# ButtonLed8.net
KiCad netlist of a schematic drawn in EAGLE
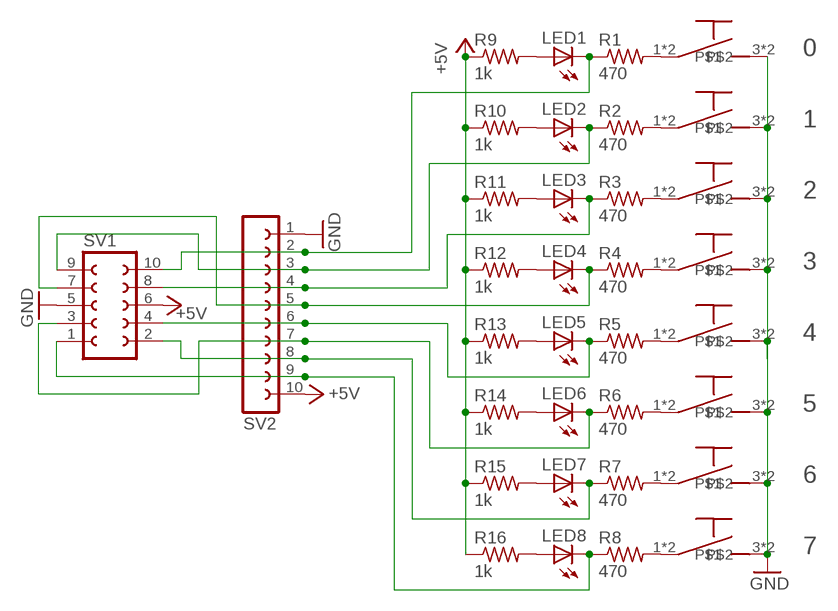
[diagram p0: schematic, sheet 1]

(export (version "E")
  (design (tool "Eeschema 10.0.6"))
  (components
    (comp (ref "LED1")
      (value "LED3MM")
      (footprint "eagle-import:LED3MM")
      (libsource (lib "eagle-import") (part "LED3MM"))
    )
    (comp (ref "LED2")
      (value "LED3MM")
      (footprint "eagle-import:LED3MM")
      (libsource (lib "eagle-import") (part "LED3MM"))
    )
    (comp (ref "LED3")
      (value "LED3MM")
      (footprint "eagle-import:LED3MM")
      (libsource (lib "eagle-import") (part "LED3MM"))
    )
    (comp (ref "LED4")
      (value "LED3MM")
      (footprint "eagle-import:LED3MM")
      (libsource (lib "eagle-import") (part "LED3MM"))
    )
    (comp (ref "LED5")
      (value "LED3MM")
      (footprint "eagle-import:LED3MM")
      (libsource (lib "eagle-import") (part "LED3MM"))
    )
    (comp (ref "LED6")
      (value "LED3MM")
      (footprint "eagle-import:LED3MM")
      (libsource (lib "eagle-import") (part "LED3MM"))
    )
    (comp (ref "LED7")
      (value "LED3MM")
      (footprint "eagle-import:LED3MM")
      (libsource (lib "eagle-import") (part "LED3MM"))
    )
    (comp (ref "LED8")
      (value "LED3MM")
      (footprint "eagle-import:LED3MM")
      (libsource (lib "eagle-import") (part "LED3MM"))
    )
    (comp (ref "R1")
      (value "470")
      (footprint "eagle-import:0204_7")
      (libsource (lib "eagle-import") (part "R-US_0204/7"))
    )
    (comp (ref "R2")
      (value "470")
      (footprint "eagle-import:0204_7")
      (libsource (lib "eagle-import") (part "R-US_0204/7"))
    )
    (comp (ref "R3")
      (value "470")
      (footprint "eagle-import:0204_7")
      (libsource (lib "eagle-import") (part "R-US_0204/7"))
    )
    (comp (ref "R4")
      (value "470")
      (footprint "eagle-import:0204_7")
      (libsource (lib "eagle-import") (part "R-US_0204/7"))
    )
    (comp (ref "R5")
      (value "470")
      (footprint "eagle-import:0204_7")
      (libsource (lib "eagle-import") (part "R-US_0204/7"))
    )
    (comp (ref "R6")
      (value "470")
      (footprint "eagle-import:0204_7")
      (libsource (lib "eagle-import") (part "R-US_0204/7"))
    )
    (comp (ref "R7")
      (value "470")
      (footprint "eagle-import:0204_7")
      (libsource (lib "eagle-import") (part "R-US_0204/7"))
    )
    (comp (ref "R8")
      (value "470")
      (footprint "eagle-import:0204_7")
      (libsource (lib "eagle-import") (part "R-US_0204/7"))
    )
    (comp (ref "R9")
      (value "1k")
      (footprint "eagle-import:0204_7")
      (libsource (lib "eagle-import") (part "R-US_0204/7"))
    )
    (comp (ref "R10")
      (value "1k")
      (footprint "eagle-import:0204_7")
      (libsource (lib "eagle-import") (part "R-US_0204/7"))
    )
    (comp (ref "R11")
      (value "1k")
      (footprint "eagle-import:0204_7")
      (libsource (lib "eagle-import") (part "R-US_0204/7"))
    )
    (comp (ref "R12")
      (value "1k")
      (footprint "eagle-import:0204_7")
      (libsource (lib "eagle-import") (part "R-US_0204/7"))
    )
    (comp (ref "R13")
      (value "1k")
      (footprint "eagle-import:0204_7")
      (libsource (lib "eagle-import") (part "R-US_0204/7"))
    )
    (comp (ref "R14")
      (value "1k")
      (footprint "eagle-import:0204_7")
      (libsource (lib "eagle-import") (part "R-US_0204/7"))
    )
    (comp (ref "R15")
      (value "1k")
      (footprint "eagle-import:0204_7")
      (libsource (lib "eagle-import") (part "R-US_0204/7"))
    )
    (comp (ref "R16")
      (value "1k")
      (footprint "eagle-import:0204_7")
      (libsource (lib "eagle-import") (part "R-US_0204/7"))
    )
    (comp (ref "SV1")
      (value "FE05-2")
      (footprint "eagle-import:FE05-2")
      (fields (field (name "OC_FARNELL") "unknown") (field (name "OC_NEWARK") "unknown"))
      (libsource (lib "eagle-import") (part "FE05-2"))
    )
    (comp (ref "SV2")
      (value "FE10-1")
      (footprint "eagle-import:FE10")
      (fields (field (name "OC_FARNELL") "unknown") (field (name "OC_NEWARK") "unknown"))
      (libsource (lib "eagle-import") (part "FE10-1"))
    )
    (comp (ref "U$1")
      (value "BUTTON")
      (footprint "eagle-import:SPARKFUN_TACTILE-PTH")
      (libsource (lib "eagle-import") (part "BUTTON"))
    )
    (comp (ref "U$2")
      (value "BUTTON")
      (footprint "eagle-import:SPARKFUN_TACTILE-PTH")
      (libsource (lib "eagle-import") (part "BUTTON"))
    )
    (comp (ref "U$3")
      (value "BUTTON")
      (footprint "eagle-import:SPARKFUN_TACTILE-PTH")
      (libsource (lib "eagle-import") (part "BUTTON"))
    )
    (comp (ref "U$4")
      (value "BUTTON")
      (footprint "eagle-import:SPARKFUN_TACTILE-PTH")
      (libsource (lib "eagle-import") (part "BUTTON"))
    )
    (comp (ref "U$5")
      (value "BUTTON")
      (footprint "eagle-import:SPARKFUN_TACTILE-PTH")
      (libsource (lib "eagle-import") (part "BUTTON"))
    )
    (comp (ref "U$6")
      (value "BUTTON")
      (footprint "eagle-import:SPARKFUN_TACTILE-PTH")
      (libsource (lib "eagle-import") (part "BUTTON"))
    )
    (comp (ref "U$7")
      (value "BUTTON")
      (footprint "eagle-import:SPARKFUN_TACTILE-PTH")
      (libsource (lib "eagle-import") (part "BUTTON"))
    )
    (comp (ref "U$8")
      (value "BUTTON")
      (footprint "eagle-import:SPARKFUN_TACTILE-PTH")
      (libsource (lib "eagle-import") (part "BUTTON"))
    )
  )
  (nets
    (net (code "1") (name "+5V") (class "Default")
      (node (ref "R10") (pin "1") (pinfunction "1_1") (pintype "passive"))
      (node (ref "R11") (pin "1") (pinfunction "1_1") (pintype "passive"))
      (node (ref "R12") (pin "1") (pinfunction "1_1") (pintype "passive"))
      (node (ref "R13") (pin "1") (pinfunction "1_1") (pintype "passive"))
      (node (ref "R14") (pin "1") (pinfunction "1_1") (pintype "passive"))
      (node (ref "R15") (pin "1") (pinfunction "1_1") (pintype "passive"))
      (node (ref "R16") (pin "1") (pinfunction "1_1") (pintype "passive"))
      (node (ref "R9") (pin "1") (pinfunction "1_1") (pintype "passive"))
      (node (ref "SV1") (pin "6") (pinfunction "6_6") (pintype "passive"))
      (node (ref "SV2") (pin "10") (pinfunction "10_10") (pintype "passive"))
    )
    (net (code "2") (name "GND") (class "Default")
      (node (ref "SV1") (pin "5") (pinfunction "5_5") (pintype "passive"))
      (node (ref "SV2") (pin "1") (pinfunction "1_1") (pintype "passive"))
      (node (ref "U$1") (pin "3") (pinfunction "P$2_3") (pintype "bidirectional"))
      (node (ref "U$1") (pin "4") (pinfunction "P$2_4") (pintype "bidirectional"))
      (node (ref "U$2") (pin "3") (pinfunction "P$2_3") (pintype "bidirectional"))
      (node (ref "U$2") (pin "4") (pinfunction "P$2_4") (pintype "bidirectional"))
      (node (ref "U$3") (pin "3") (pinfunction "P$2_3") (pintype "bidirectional"))
      (node (ref "U$3") (pin "4") (pinfunction "P$2_4") (pintype "bidirectional"))
      (node (ref "U$4") (pin "3") (pinfunction "P$2_3") (pintype "bidirectional"))
      (node (ref "U$4") (pin "4") (pinfunction "P$2_4") (pintype "bidirectional"))
      (node (ref "U$5") (pin "3") (pinfunction "P$2_3") (pintype "bidirectional"))
      (node (ref "U$5") (pin "4") (pinfunction "P$2_4") (pintype "bidirectional"))
      (node (ref "U$6") (pin "3") (pinfunction "P$2_3") (pintype "bidirectional"))
      (node (ref "U$6") (pin "4") (pinfunction "P$2_4") (pintype "bidirectional"))
      (node (ref "U$7") (pin "3") (pinfunction "P$2_3") (pintype "bidirectional"))
      (node (ref "U$7") (pin "4") (pinfunction "P$2_4") (pintype "bidirectional"))
      (node (ref "U$8") (pin "3") (pinfunction "P$2_3") (pintype "bidirectional"))
      (node (ref "U$8") (pin "4") (pinfunction "P$2_4") (pintype "bidirectional"))
    )
    (net (code "3") (name "Net-(LED1-C)") (class "Default")
      (node (ref "LED1") (pin "K") (pinfunction "C_K") (pintype "passive"))
      (node (ref "R1") (pin "1") (pinfunction "1_1") (pintype "passive"))
      (node (ref "SV1") (pin "10") (pinfunction "10_10") (pintype "passive"))
      (node (ref "SV2") (pin "2") (pinfunction "2_2") (pintype "passive"))
    )
    (net (code "4") (name "Net-(LED1-PadA)") (class "Default")
      (node (ref "LED1") (pin "A") (pinfunction "A_A") (pintype "passive"))
      (node (ref "R9") (pin "2") (pinfunction "2_2") (pintype "passive"))
    )
    (net (code "5") (name "Net-(LED2-C)") (class "Default")
      (node (ref "LED2") (pin "K") (pinfunction "C_K") (pintype "passive"))
      (node (ref "R2") (pin "1") (pinfunction "1_1") (pintype "passive"))
      (node (ref "SV1") (pin "9") (pinfunction "9_9") (pintype "passive"))
      (node (ref "SV2") (pin "3") (pinfunction "3_3") (pintype "passive"))
    )
    (net (code "6") (name "Net-(LED2-PadA)") (class "Default")
      (node (ref "LED2") (pin "A") (pinfunction "A_A") (pintype "passive"))
      (node (ref "R10") (pin "2") (pinfunction "2_2") (pintype "passive"))
    )
    (net (code "7") (name "Net-(LED3-C)") (class "Default")
      (node (ref "LED3") (pin "K") (pinfunction "C_K") (pintype "passive"))
      (node (ref "R3") (pin "1") (pinfunction "1_1") (pintype "passive"))
      (node (ref "SV1") (pin "8") (pinfunction "8_8") (pintype "passive"))
      (node (ref "SV2") (pin "4") (pinfunction "4_4") (pintype "passive"))
    )
    (net (code "8") (name "Net-(LED3-PadA)") (class "Default")
      (node (ref "LED3") (pin "A") (pinfunction "A_A") (pintype "passive"))
      (node (ref "R11") (pin "2") (pinfunction "2_2") (pintype "passive"))
    )
    (net (code "9") (name "Net-(LED4-C)") (class "Default")
      (node (ref "LED4") (pin "K") (pinfunction "C_K") (pintype "passive"))
      (node (ref "R4") (pin "1") (pinfunction "1_1") (pintype "passive"))
      (node (ref "SV1") (pin "7") (pinfunction "7_7") (pintype "passive"))
      (node (ref "SV2") (pin "5") (pinfunction "5_5") (pintype "passive"))
    )
    (net (code "10") (name "Net-(LED4-PadA)") (class "Default")
      (node (ref "LED4") (pin "A") (pinfunction "A_A") (pintype "passive"))
      (node (ref "R12") (pin "2") (pinfunction "2_2") (pintype "passive"))
    )
    (net (code "11") (name "Net-(LED5-C)") (class "Default")
      (node (ref "LED5") (pin "K") (pinfunction "C_K") (pintype "passive"))
      (node (ref "R5") (pin "1") (pinfunction "1_1") (pintype "passive"))
      (node (ref "SV1") (pin "4") (pinfunction "4_4") (pintype "passive"))
      (node (ref "SV2") (pin "6") (pinfunction "6_6") (pintype "passive"))
    )
    (net (code "12") (name "Net-(LED5-PadA)") (class "Default")
      (node (ref "LED5") (pin "A") (pinfunction "A_A") (pintype "passive"))
      (node (ref "R13") (pin "2") (pinfunction "2_2") (pintype "passive"))
    )
    (net (code "13") (name "Net-(LED6-C)") (class "Default")
      (node (ref "LED6") (pin "K") (pinfunction "C_K") (pintype "passive"))
      (node (ref "R6") (pin "1") (pinfunction "1_1") (pintype "passive"))
      (node (ref "SV1") (pin "3") (pinfunction "3_3") (pintype "passive"))
      (node (ref "SV2") (pin "7") (pinfunction "7_7") (pintype "passive"))
    )
    (net (code "14") (name "Net-(LED6-PadA)") (class "Default")
      (node (ref "LED6") (pin "A") (pinfunction "A_A") (pintype "passive"))
      (node (ref "R14") (pin "2") (pinfunction "2_2") (pintype "passive"))
    )
    (net (code "15") (name "Net-(LED7-C)") (class "Default")
      (node (ref "LED7") (pin "K") (pinfunction "C_K") (pintype "passive"))
      (node (ref "R7") (pin "1") (pinfunction "1_1") (pintype "passive"))
      (node (ref "SV1") (pin "2") (pinfunction "2_2") (pintype "passive"))
      (node (ref "SV2") (pin "8") (pinfunction "8_8") (pintype "passive"))
    )
    (net (code "16") (name "Net-(LED7-PadA)") (class "Default")
      (node (ref "LED7") (pin "A") (pinfunction "A_A") (pintype "passive"))
      (node (ref "R15") (pin "2") (pinfunction "2_2") (pintype "passive"))
    )
    (net (code "17") (name "Net-(LED8-C)") (class "Default")
      (node (ref "LED8") (pin "K") (pinfunction "C_K") (pintype "passive"))
      (node (ref "R8") (pin "1") (pinfunction "1_1") (pintype "passive"))
      (node (ref "SV1") (pin "1") (pinfunction "1_1") (pintype "passive"))
      (node (ref "SV2") (pin "9") (pinfunction "9_9") (pintype "passive"))
    )
    (net (code "18") (name "Net-(LED8-PadA)") (class "Default")
      (node (ref "LED8") (pin "A") (pinfunction "A_A") (pintype "passive"))
      (node (ref "R16") (pin "2") (pinfunction "2_2") (pintype "passive"))
    )
    (net (code "19") (name "Net-(R1-Pad2)") (class "Default")
      (node (ref "R1") (pin "2") (pinfunction "2_2") (pintype "passive"))
      (node (ref "U$1") (pin "1") (pinfunction "P$1_1") (pintype "bidirectional"))
      (node (ref "U$1") (pin "2") (pinfunction "P$1_2") (pintype "bidirectional"))
    )
    (net (code "20") (name "Net-(R2-Pad2)") (class "Default")
      (node (ref "R2") (pin "2") (pinfunction "2_2") (pintype "passive"))
      (node (ref "U$2") (pin "1") (pinfunction "P$1_1") (pintype "bidirectional"))
      (node (ref "U$2") (pin "2") (pinfunction "P$1_2") (pintype "bidirectional"))
    )
    (net (code "21") (name "Net-(R3-Pad2)") (class "Default")
      (node (ref "R3") (pin "2") (pinfunction "2_2") (pintype "passive"))
      (node (ref "U$3") (pin "1") (pinfunction "P$1_1") (pintype "bidirectional"))
      (node (ref "U$3") (pin "2") (pinfunction "P$1_2") (pintype "bidirectional"))
    )
    (net (code "22") (name "Net-(R4-Pad2)") (class "Default")
      (node (ref "R4") (pin "2") (pinfunction "2_2") (pintype "passive"))
      (node (ref "U$4") (pin "1") (pinfunction "P$1_1") (pintype "bidirectional"))
      (node (ref "U$4") (pin "2") (pinfunction "P$1_2") (pintype "bidirectional"))
    )
    (net (code "23") (name "Net-(R5-Pad2)") (class "Default")
      (node (ref "R5") (pin "2") (pinfunction "2_2") (pintype "passive"))
      (node (ref "U$5") (pin "1") (pinfunction "P$1_1") (pintype "bidirectional"))
      (node (ref "U$5") (pin "2") (pinfunction "P$1_2") (pintype "bidirectional"))
    )
    (net (code "24") (name "Net-(R6-Pad2)") (class "Default")
      (node (ref "R6") (pin "2") (pinfunction "2_2") (pintype "passive"))
      (node (ref "U$6") (pin "1") (pinfunction "P$1_1") (pintype "bidirectional"))
      (node (ref "U$6") (pin "2") (pinfunction "P$1_2") (pintype "bidirectional"))
    )
    (net (code "25") (name "Net-(R7-Pad2)") (class "Default")
      (node (ref "R7") (pin "2") (pinfunction "2_2") (pintype "passive"))
      (node (ref "U$7") (pin "1") (pinfunction "P$1_1") (pintype "bidirectional"))
      (node (ref "U$7") (pin "2") (pinfunction "P$1_2") (pintype "bidirectional"))
    )
    (net (code "26") (name "Net-(R8-Pad2)") (class "Default")
      (node (ref "R8") (pin "2") (pinfunction "2_2") (pintype "passive"))
      (node (ref "U$8") (pin "1") (pinfunction "P$1_1") (pintype "bidirectional"))
      (node (ref "U$8") (pin "2") (pinfunction "P$1_2") (pintype "bidirectional"))
    )
  )
)
